# 468323_001_USB-UART.net
KiCad netlist of a schematic drawn in Altium Designer
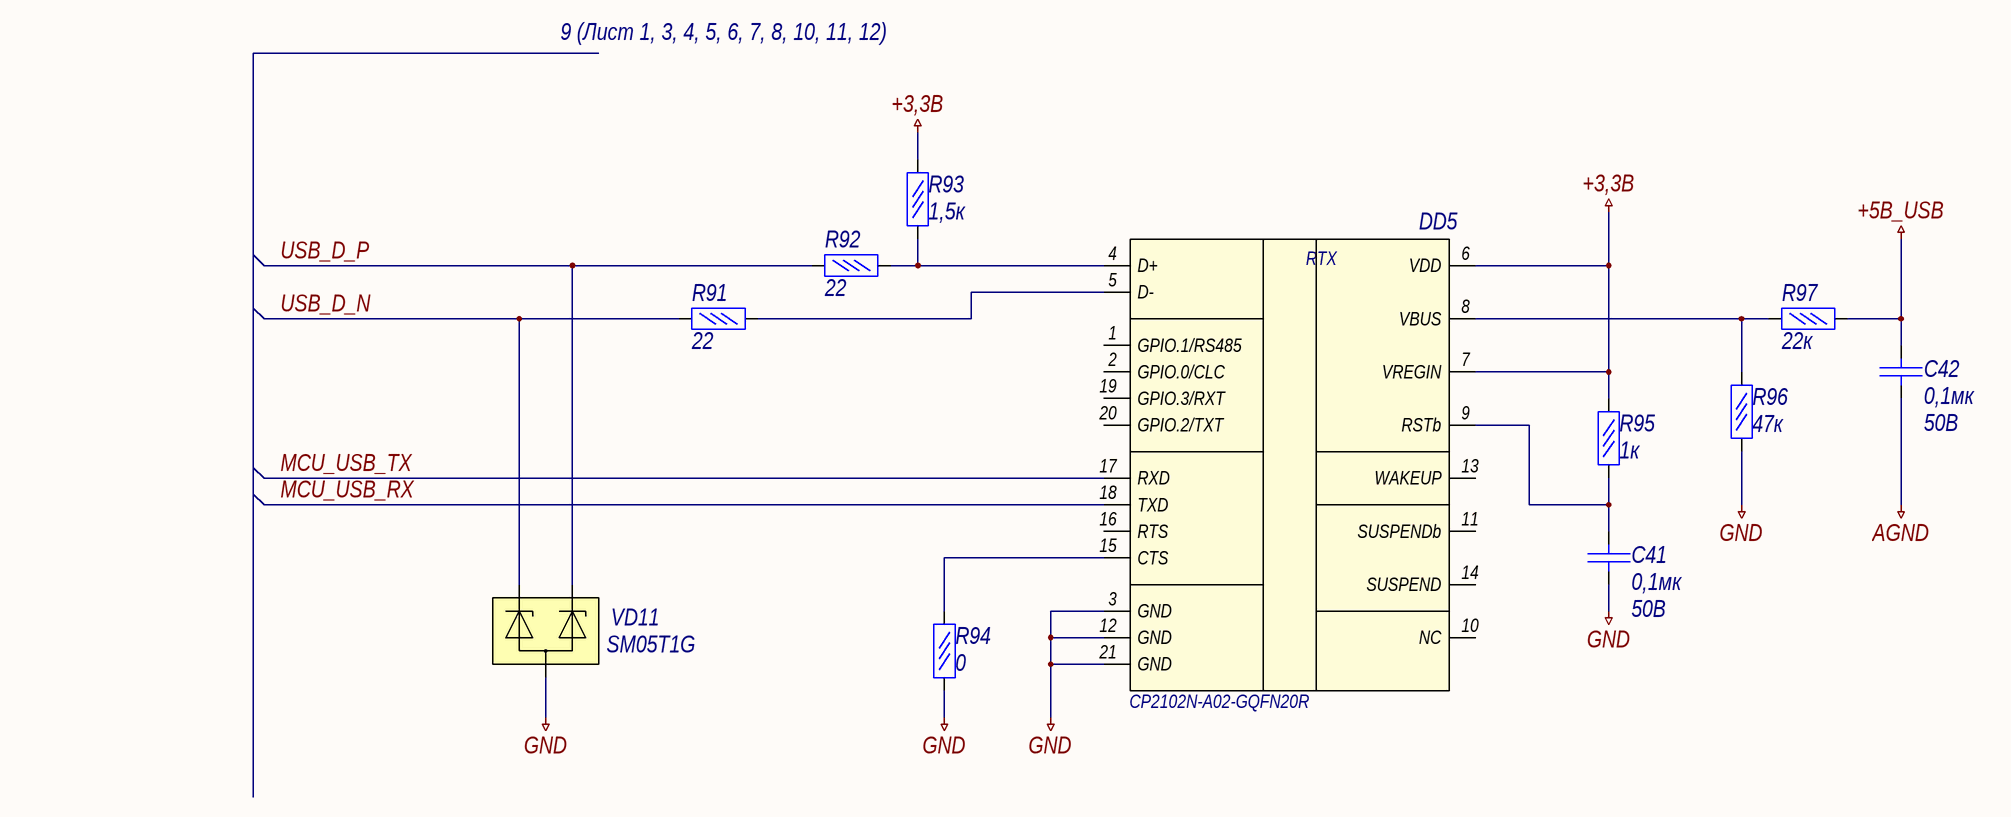
[diagram p0: РЕУН.468323.001_USB-UART.SchDoc]

(export (version "E")
  (design (tool "Eeschema 10.0.6"))
  (components
    (comp (ref "C41")
      (value "0,1мк")
      (footprint "C0805_AA")
      (description "Конденсатор кер.")
      (fields (field (name "VOLTAGE") "50В"))
      (libsource (lib "Library_Diana") (part "Конденсатор кер."))
    )
    (comp (ref "C42")
      (value "0,1мк")
      (footprint "C0805_AA")
      (description "Конденсатор кер.")
      (fields (field (name "VOLTAGE") "50В"))
      (libsource (lib "Library_Diana") (part "Конденсатор кер."))
    )
    (comp (ref "DD5")
      (value "CP2102N-A02-GQFN20R")
      (description "USB-UART преобразователь")
      (libsource (lib "Library_Diana") (part "CP2102N-A02-GQFN20R"))
    )
    (comp (ref "R91")
      (value "22")
      (footprint "R1206")
      (description "Резистор 0,05Вт")
      (libsource (lib "") (part "Резистор  0,05Вт_1"))
    )
    (comp (ref "R92")
      (value "22")
      (footprint "R1206")
      (description "Резистор 0,05Вт")
      (libsource (lib "") (part "Резистор  0,05Вт_1"))
    )
    (comp (ref "R93")
      (value "~")
      (footprint "R1206")
      (description "Резистор 0,05Вт")
      (fields (field (name "5") "1,5к"))
      (libsource (lib "Library_Diana") (part "Резистор  0,05Вт"))
    )
    (comp (ref "R94")
      (value "0")
      (footprint "R1206")
      (description "Резистор 0,05Вт")
      (libsource (lib "Library_Diana") (part "Резистор  0,05Вт"))
    )
    (comp (ref "R95")
      (value "1к")
      (footprint "R1206")
      (description "Резистор 0,05Вт")
      (libsource (lib "Library_Diana") (part "Резистор  0,05Вт"))
    )
    (comp (ref "R96")
      (value "47к")
      (footprint "R1206")
      (description "Резистор 0,05Вт")
      (libsource (lib "Library_Diana") (part "Резистор  0,05Вт"))
    )
    (comp (ref "R97")
      (value "22к")
      (footprint "R1206")
      (description "Резистор 0,05Вт")
      (libsource (lib "") (part "Резистор  0,05Вт_1"))
    )
    (comp (ref "VD11")
      (value "SM05T1G")
      (description "Сборка TVS-диодов")
      (libsource (lib "Library_Diana") (part "ZenerArray2"))
    )
  )
  (nets
    (net (code "1") (name "+3,3В") (class "Default")
      (node (ref "DD5") (pin "6") (pinfunction "VDD_6") (pintype "passive"))
      (node (ref "DD5") (pin "7") (pinfunction "VREGIN_7") (pintype "passive"))
      (node (ref "R93") (pin "2") (pinfunction "2_2") (pintype "passive"))
      (node (ref "R95") (pin "2") (pinfunction "2_2") (pintype "passive"))
    )
    (net (code "2") (name "+5В_USB") (class "Default")
      (node (ref "C42") (pin "2") (pinfunction "2_2") (pintype "passive"))
      (node (ref "R97") (pin "2") (pinfunction "2_2") (pintype "passive"))
    )
    (net (code "3") (name "/MCU_USB_RX") (class "Default")
      (node (ref "DD5") (pin "18") (pinfunction "TXD_18") (pintype "passive"))
    )
    (net (code "4") (name "/MCU_USB_TX") (class "Default")
      (node (ref "DD5") (pin "17") (pinfunction "RXD_17") (pintype "passive"))
    )
    (net (code "5") (name "/USB_D_N") (class "Default")
      (node (ref "R91") (pin "1") (pinfunction "1_1") (pintype "passive"))
      (node (ref "VD11") (pin "1") (pintype "passive"))
    )
    (net (code "6") (name "/USB_D_P") (class "Default")
      (node (ref "R92") (pin "1") (pinfunction "1_1") (pintype "passive"))
      (node (ref "VD11") (pin "2") (pintype "passive"))
    )
    (net (code "7") (name "AGND") (class "Default")
      (node (ref "C42") (pin "1") (pinfunction "1_1") (pintype "passive"))
    )
    (net (code "8") (name "GND") (class "Default")
      (node (ref "C41") (pin "1") (pinfunction "1_1") (pintype "passive"))
      (node (ref "DD5") (pin "12") (pinfunction "GND_12") (pintype "passive"))
      (node (ref "DD5") (pin "21") (pinfunction "GND_21") (pintype "passive"))
      (node (ref "DD5") (pin "3") (pinfunction "GND_3") (pintype "passive"))
      (node (ref "R94") (pin "1") (pinfunction "1_1") (pintype "passive"))
      (node (ref "R96") (pin "1") (pinfunction "1_1") (pintype "passive"))
      (node (ref "VD11") (pin "3") (pintype "passive"))
    )
    (net (code "9") (name "Net-(DD5-CTS)") (class "Default")
      (node (ref "DD5") (pin "15") (pinfunction "CTS_15") (pintype "passive"))
      (node (ref "R94") (pin "2") (pinfunction "2_2") (pintype "passive"))
    )
    (net (code "10") (name "Net-(DD5-D+)") (class "Default")
      (node (ref "DD5") (pin "4") (pinfunction "D+_4") (pintype "passive"))
      (node (ref "R92") (pin "2") (pinfunction "2_2") (pintype "passive"))
      (node (ref "R93") (pin "1") (pinfunction "1_1") (pintype "passive"))
    )
    (net (code "11") (name "Net-(DD5-D-)") (class "Default")
      (node (ref "DD5") (pin "5") (pinfunction "D-_5") (pintype "passive"))
      (node (ref "R91") (pin "2") (pinfunction "2_2") (pintype "passive"))
    )
    (net (code "12") (name "Net-(DD5-RSTb)") (class "Default")
      (node (ref "C41") (pin "2") (pinfunction "2_2") (pintype "passive"))
      (node (ref "DD5") (pin "9") (pinfunction "RSTb_9") (pintype "passive"))
      (node (ref "R95") (pin "1") (pinfunction "1_1") (pintype "passive"))
    )
    (net (code "13") (name "Net-(DD5-VBUS)") (class "Default")
      (node (ref "DD5") (pin "8") (pinfunction "VBUS_8") (pintype "passive"))
      (node (ref "R96") (pin "2") (pinfunction "2_2") (pintype "passive"))
      (node (ref "R97") (pin "1") (pinfunction "1_1") (pintype "passive"))
    )
    (net (code "14") (name "unconnected-(DD5-GPIO.0{slash}CLC-Pad2)") (class "Default")
      (node (ref "DD5") (pin "2") (pinfunction "GPIO.0/CLC_2") (pintype "passive"))
    )
    (net (code "15") (name "unconnected-(DD5-GPIO.1{slash}RS485-Pad1)") (class "Default")
      (node (ref "DD5") (pin "1") (pinfunction "GPIO.1/RS485_1") (pintype "passive"))
    )
    (net (code "16") (name "unconnected-(DD5-GPIO.2{slash}TXT-Pad20)") (class "Default")
      (node (ref "DD5") (pin "20") (pinfunction "GPIO.2/TXT_20") (pintype "passive"))
    )
    (net (code "17") (name "unconnected-(DD5-GPIO.3{slash}RXT-Pad19)") (class "Default")
      (node (ref "DD5") (pin "19") (pinfunction "GPIO.3/RXT_19") (pintype "passive"))
    )
    (net (code "18") (name "unconnected-(DD5-NC-Pad10)") (class "Default")
      (node (ref "DD5") (pin "10") (pinfunction "NC_10") (pintype "passive"))
    )
    (net (code "19") (name "unconnected-(DD5-RTS-Pad16)") (class "Default")
      (node (ref "DD5") (pin "16") (pinfunction "RTS_16") (pintype "passive"))
    )
    (net (code "20") (name "unconnected-(DD5-SUSPEND-Pad14)") (class "Default")
      (node (ref "DD5") (pin "14") (pinfunction "SUSPEND_14") (pintype "passive"))
    )
    (net (code "21") (name "unconnected-(DD5-SUSPENDb-Pad11)") (class "Default")
      (node (ref "DD5") (pin "11") (pinfunction "SUSPENDb_11") (pintype "passive"))
    )
    (net (code "22") (name "unconnected-(DD5-WAKEUP-Pad13)") (class "Default")
      (node (ref "DD5") (pin "13") (pinfunction "WAKEUP_13") (pintype "passive"))
    )
  )
)
